# zerocam2S_revD.net
KiCad netlist of a schematic drawn in EAGLE
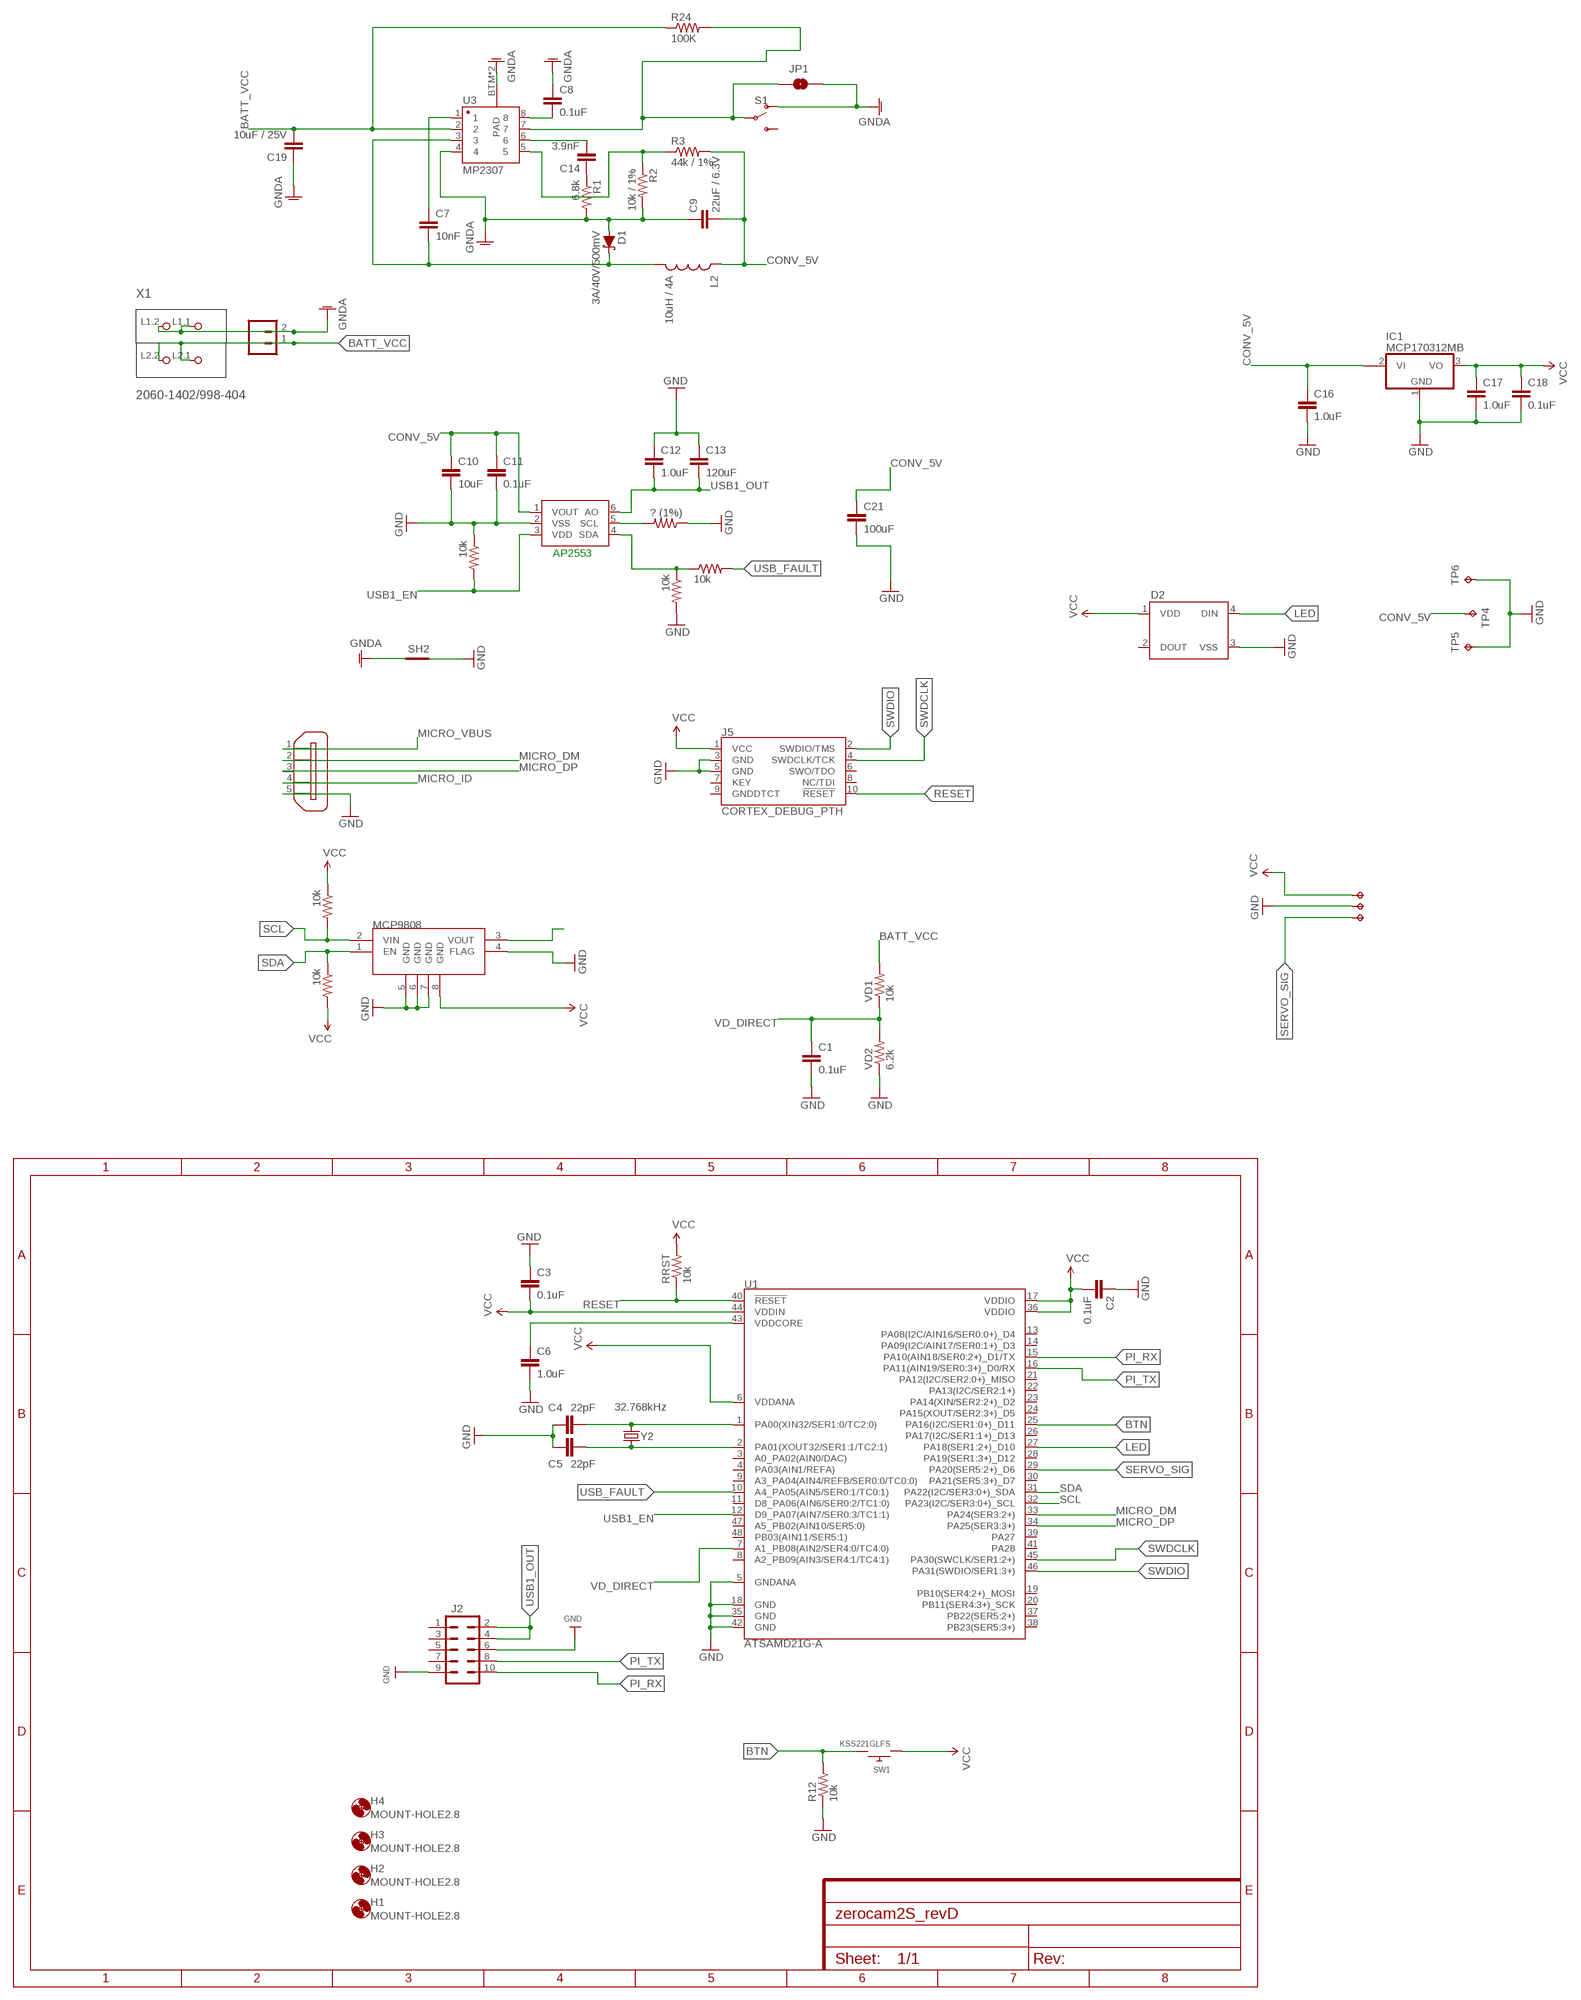
[diagram p0: schematic, sheet 1]

(export (version "E")
  (design (tool "Eeschema 10.0.6"))
  (components
    (comp (ref "AP2553")
      (value "MCP4725")
      (footprint "eagle-import:SOT23-6")
      (libsource (lib "eagle-import") (part "MCP4725SOT-23"))
    )
    (comp (ref "C1")
      (value "0.1uF")
      (footprint "eagle-import:0805")
      (libsource (lib "eagle-import") (part "CAP0805"))
    )
    (comp (ref "C2")
      (value "0.1uF")
      (footprint "eagle-import:0805")
      (libsource (lib "eagle-import") (part "1.0UF-0805-25V-10%"))
    )
    (comp (ref "C3")
      (value "0.1uF")
      (footprint "eagle-import:0805")
      (libsource (lib "eagle-import") (part "1.0UF-0805-25V-10%"))
    )
    (comp (ref "C4")
      (value "22pF")
      (footprint "eagle-import:0805")
      (libsource (lib "eagle-import") (part "SparkFun-Passives_CAP0805"))
    )
    (comp (ref "C5")
      (value "22pF")
      (footprint "eagle-import:0805")
      (libsource (lib "eagle-import") (part "SparkFun-Passives_CAP0805"))
    )
    (comp (ref "C6")
      (value "1.0uF")
      (footprint "eagle-import:0805")
      (libsource (lib "eagle-import") (part "1.0UF-0805-25V-10%"))
    )
    (comp (ref "C7")
      (value "10nF")
      (footprint "eagle-import:0805")
      (libsource (lib "eagle-import") (part "CAP0805"))
    )
    (comp (ref "C8")
      (value "0.1uF")
      (footprint "eagle-import:1206")
      (libsource (lib "eagle-import") (part "CAP1206"))
    )
    (comp (ref "C9")
      (value "22uF / 6.3V")
      (footprint "eagle-import:1210")
      (libsource (lib "eagle-import") (part "CAP1210"))
    )
    (comp (ref "C10")
      (value "10uF")
      (footprint "eagle-import:0805")
      (libsource (lib "eagle-import") (part "1.0UF-0805-25V-10%"))
    )
    (comp (ref "C11")
      (value "0.1uF")
      (footprint "eagle-import:0805")
      (libsource (lib "eagle-import") (part "1.0UF-0805-25V-10%"))
    )
    (comp (ref "C12")
      (value "1.0uF")
      (footprint "eagle-import:1206")
      (libsource (lib "eagle-import") (part "1.0UF-1206-50V-10%"))
    )
    (comp (ref "C13")
      (value "120uF")
      (footprint "eagle-import:1206")
      (libsource (lib "eagle-import") (part "1.0UF-1206-50V-10%"))
    )
    (comp (ref "C14")
      (value "3.9nF")
      (footprint "eagle-import:1206")
      (libsource (lib "eagle-import") (part "CAP1206"))
    )
    (comp (ref "C16")
      (value "1.0uF")
      (footprint "eagle-import:0805")
      (libsource (lib "eagle-import") (part "1.0UF-0805-25V-10%"))
    )
    (comp (ref "C17")
      (value "1.0uF")
      (footprint "eagle-import:1206")
      (libsource (lib "eagle-import") (part "1.0UF-1206-50V-10%"))
    )
    (comp (ref "C18")
      (value "0.1uF")
      (footprint "eagle-import:0805")
      (libsource (lib "eagle-import") (part "1.0UF-0805-25V-10%"))
    )
    (comp (ref "C19")
      (value "10uF / 25V")
      (footprint "eagle-import:1210")
      (libsource (lib "eagle-import") (part "CAP1210"))
    )
    (comp (ref "C21")
      (value "100uF")
      (footprint "eagle-import:1210")
      (libsource (lib "eagle-import") (part "10UF-1210-50V-20%"))
    )
    (comp (ref "D1")
      (value "3A/40V/500mV")
      (footprint "eagle-import:SMA-DIODE")
      (libsource (lib "eagle-import") (part "DIODE-SCHOTTKY-B340A"))
    )
    (comp (ref "D2")
      (value "WS2812B")
      (footprint "eagle-import:WS2812B")
      (libsource (lib "eagle-import") (part "WS2812B"))
    )
    (comp (ref "H1")
      (value "MOUNT-HOLE2.8")
      (footprint "eagle-import:2,8")
      (libsource (lib "eagle-import") (part "MOUNT-HOLE2.8"))
    )
    (comp (ref "H2")
      (value "MOUNT-HOLE2.8")
      (footprint "eagle-import:2,8")
      (libsource (lib "eagle-import") (part "MOUNT-HOLE2.8"))
    )
    (comp (ref "H3")
      (value "MOUNT-HOLE2.8")
      (footprint "eagle-import:2,8")
      (libsource (lib "eagle-import") (part "MOUNT-HOLE2.8"))
    )
    (comp (ref "H4")
      (value "MOUNT-HOLE2.8")
      (footprint "eagle-import:2,8")
      (libsource (lib "eagle-import") (part "MOUNT-HOLE2.8"))
    )
    (comp (ref "IC1")
      (value "MCP170312MB")
      (footprint "eagle-import:SOT89")
      (libsource (lib "eagle-import") (part "MCP1703MB12"))
    )
    (comp (ref "J1")
      (value "CONN_023.5MM-NO_SILK")
      (footprint "eagle-import:SCREWTERMINAL-3.5MM-2-NS")
      (libsource (lib "eagle-import") (part "CONN_023.5MM-NO_SILK"))
    )
    (comp (ref "J2")
      (value "M05X2PTH")
      (footprint "eagle-import:AVR_ICSP")
      (libsource (lib "eagle-import") (part "M05X2PTH"))
    )
    (comp (ref "J5")
      (value "CORTEX_DEBUG_PTH")
      (footprint "eagle-import:2X5-PTH-1.27MM")
      (libsource (lib "eagle-import") (part "CORTEX_DEBUG_PTH"))
    )
    (comp (ref "JP1")
      (value "JUMPER-SMT_2_NO_NO-SILK")
      (footprint "eagle-import:SMT-JUMPER_2_NO_NO-SILK")
      (libsource (lib "eagle-import") (part "JUMPER-SMT_2_NO_NO-SILK"))
    )
    (comp (ref "L2")
      (value "10uH / 4A")
      (footprint "eagle-import:SRU1038")
      (libsource (lib "eagle-import") (part "INDUCTORSRU1038"))
    )
    (comp (ref "MCP9808")
      (value "V_REG_MIC5216")
      (footprint "eagle-import:MSOP8")
      (libsource (lib "eagle-import") (part "V_REG_MIC5216"))
    )
    (comp (ref "R1")
      (value "6.8k")
      (footprint "eagle-import:1206")
      (libsource (lib "eagle-import") (part "SparkFun-Resistors_RESISTOR1206"))
    )
    (comp (ref "R2")
      (value "10k / 1%")
      (footprint "eagle-import:1206")
      (libsource (lib "eagle-import") (part "SparkFun-Resistors_RESISTOR1206"))
    )
    (comp (ref "R3")
      (value "44k / 1%")
      (footprint "eagle-import:1206")
      (libsource (lib "eagle-import") (part "SparkFun-Resistors_RESISTOR1206"))
    )
    (comp (ref "R12")
      (value "10k")
      (footprint "eagle-import:0805")
      (libsource (lib "eagle-import") (part "RESISTOR0805-RES"))
    )
    (comp (ref "R24")
      (value "100K")
      (footprint "eagle-import:1206")
      (libsource (lib "eagle-import") (part "SparkFun-Resistors_RESISTOR1206"))
    )
    (comp (ref "RRST")
      (value "10k")
      (footprint "eagle-import:0805")
      (libsource (lib "eagle-import") (part "RESISTOR0805-RES"))
    )
    (comp (ref "R_I2C_1")
      (value "10k")
      (footprint "eagle-import:0805")
      (libsource (lib "eagle-import") (part "RESISTOR0805-RES"))
    )
    (comp (ref "R_I2C_2")
      (value "10k")
      (footprint "eagle-import:0805")
      (libsource (lib "eagle-import") (part "RESISTOR0805-RES"))
    )
    (comp (ref "R_MOSFET_USB1")
      (value "? (1%)")
      (footprint "eagle-import:0805")
      (libsource (lib "eagle-import") (part "RESISTOR0805-RES"))
    )
    (comp (ref "R_MOSFET_USB2")
      (value "10k")
      (footprint "eagle-import:0805")
      (libsource (lib "eagle-import") (part "RESISTOR0805-RES"))
    )
    (comp (ref "R_MOSFET_USB3")
      (value "10k")
      (footprint "eagle-import:0805")
      (libsource (lib "eagle-import") (part "RESISTOR0805-RES"))
    )
    (comp (ref "R_MOSFET_USB4")
      (value "10k")
      (footprint "eagle-import:0805")
      (libsource (lib "eagle-import") (part "RESISTOR0805-RES"))
    )
    (comp (ref "S1")
      (value "SWITCH-SPDT-SMD-RIGHT-ANGLE")
      (footprint "eagle-import:SWITCH_SPST_SMD_A")
      (libsource (lib "eagle-import") (part "SWITCH-SPDT-SMD-RIGHT-ANGLE"))
    )
    (comp (ref "SH2")
      (value "SHORT-HT5")
      (footprint "eagle-import:SHORT_TOP-50")
      (libsource (lib "eagle-import") (part "SHORT-HT5"))
    )
    (comp (ref "SW1")
      (value "KSS221GLFS")
      (footprint "eagle-import:BTN_CK_KSS")
      (libsource (lib "eagle-import") (part "SWITCH_PUSHBUTTONC&K_KSS"))
    )
    (comp (ref "TP1")
      (value "TPPAD1-13Y")
      (footprint "eagle-import:P1-13Y")
      (libsource (lib "eagle-import") (part "TPPAD1-13Y"))
    )
    (comp (ref "TP2")
      (value "TPPAD1-13Y")
      (footprint "eagle-import:P1-13Y")
      (libsource (lib "eagle-import") (part "TPPAD1-13Y"))
    )
    (comp (ref "TP3")
      (value "TPPAD1-13Y")
      (footprint "eagle-import:P1-13Y")
      (libsource (lib "eagle-import") (part "TPPAD1-13Y"))
    )
    (comp (ref "TP4")
      (value "TPB2,54")
      (footprint "eagle-import:B2,54")
      (libsource (lib "eagle-import") (part "TPB2,54"))
    )
    (comp (ref "TP5")
      (value "TPB2,54")
      (footprint "eagle-import:B2,54")
      (libsource (lib "eagle-import") (part "TPB2,54"))
    )
    (comp (ref "TP6")
      (value "TPB2,54")
      (footprint "eagle-import:B2,54")
      (libsource (lib "eagle-import") (part "TPB2,54"))
    )
    (comp (ref "U1")
      (value "ATSAMD21G-A")
      (footprint "eagle-import:TQFP-48")
      (libsource (lib "eagle-import") (part "ATSAMD21G-A"))
    )
    (comp (ref "U3")
      (value "MP2307")
      (footprint "eagle-import:SO08")
      (libsource (lib "eagle-import") (part "GENERIC-SOIC8MSGEQ7N-FILTER"))
    )
    (comp (ref "VD1")
      (value "10k")
      (footprint "eagle-import:0805")
      (libsource (lib "eagle-import") (part "RESISTOR0805-RES"))
    )
    (comp (ref "VD2")
      (value "6.2k")
      (footprint "eagle-import:0805")
      (libsource (lib "eagle-import") (part "RESISTOR0805-RES"))
    )
    (comp (ref "X1")
      (value "2060-1402/998-404")
      (footprint "eagle-import:P-2060-1402_998-404")
      (libsource (lib "eagle-import") (part "2060-1402/998-404"))
    )
    (comp (ref "X2")
      (value "ZX62D-B-5PA8")
      (footprint "eagle-import:ZX62D-B-5PA8")
      (fields (field (name "MF") "Hirose"))
      (libsource (lib "eagle-import") (part "ZX62D-B-5PA8"))
    )
    (comp (ref "Y2")
      (value "32.768kHz")
      (footprint "eagle-import:CRYSTAL-SMD-3.2X1.5MM")
      (libsource (lib "eagle-import") (part "CRYSTAL3.2X1.5MM"))
    )
  )
  (nets
    (net (code "1") (name "/CONV_5V") (class "Default")
      (node (ref "AP2553") (pin "1") (pinfunction "VOUT_1") (pintype "bidirectional"))
      (node (ref "C10") (pin "1") (pinfunction "1_1") (pintype "passive"))
      (node (ref "C11") (pin "1") (pinfunction "1_1") (pintype "passive"))
      (node (ref "C16") (pin "1") (pinfunction "1_1") (pintype "passive"))
      (node (ref "C21") (pin "1") (pinfunction "1_1") (pintype "passive"))
      (node (ref "C9") (pin "2") (pinfunction "2_2") (pintype "passive"))
      (node (ref "IC1") (pin "2@1") (pinfunction "VI1_2@1") (pintype "input"))
      (node (ref "L2") (pin "1") (pinfunction "1_1") (pintype "passive"))
      (node (ref "R3") (pin "2") (pinfunction "2_2") (pintype "passive"))
      (node (ref "TP4") (pin "TP") (pinfunction "TP_TP") (pintype "input"))
    )
    (net (code "2") (name "/MICRO_DM") (class "Default")
      (node (ref "U1") (pin "33") (pinfunction "PA24(SER3:2+)_33") (pintype "bidirectional"))
      (node (ref "X2") (pin "2") (pinfunction "2_2") (pintype "passive"))
    )
    (net (code "3") (name "/MICRO_DP") (class "Default")
      (node (ref "U1") (pin "34") (pinfunction "PA25(SER3:3+)_34") (pintype "bidirectional"))
      (node (ref "X2") (pin "3") (pinfunction "3_3") (pintype "passive"))
    )
    (net (code "4") (name "/MICRO_ID") (class "Default")
      (node (ref "X2") (pin "4") (pinfunction "4_4") (pintype "passive"))
    )
    (net (code "5") (name "/MICRO_VBUS") (class "Default")
      (node (ref "X2") (pin "1") (pinfunction "1_1") (pintype "passive"))
    )
    (net (code "6") (name "/USB1_EN") (class "Default")
      (node (ref "AP2553") (pin "3") (pinfunction "VDD_3") (pintype "bidirectional"))
      (node (ref "R_MOSFET_USB3") (pin "2") (pinfunction "2_2") (pintype "passive"))
      (node (ref "U1") (pin "12") (pinfunction "D9_PA07(AIN7/SER0:3/TC1:1)_12") (pintype "bidirectional"))
    )
    (net (code "7") (name "/VD_DIRECT") (class "Default")
      (node (ref "C1") (pin "1") (pinfunction "1_1") (pintype "passive"))
      (node (ref "U1") (pin "7") (pinfunction "A1_PB08(AIN2/SER4:0/TC4:0)_7") (pintype "bidirectional"))
      (node (ref "VD1") (pin "1") (pinfunction "1_1") (pintype "passive"))
      (node (ref "VD2") (pin "2") (pinfunction "2_2") (pintype "passive"))
    )
    (net (code "8") (name "BATT_VCC") (class "Default")
      (node (ref "C19") (pin "2") (pinfunction "2_2") (pintype "passive"))
      (node (ref "J1") (pin "1") (pinfunction "1_1") (pintype "passive"))
      (node (ref "R24") (pin "1") (pinfunction "1_1") (pintype "passive"))
      (node (ref "U3") (pin "2") (pinfunction "2_2") (pintype "bidirectional"))
      (node (ref "VD1") (pin "2") (pinfunction "2_2") (pintype "passive"))
      (node (ref "X1") (pin "L2.1") (pinfunction "P2.1_L2.1") (pintype "bidirectional"))
      (node (ref "X1") (pin "L2.2") (pinfunction "P2.2_L2.2") (pintype "bidirectional"))
    )
    (net (code "9") (name "BTN") (class "Default")
      (node (ref "R12") (pin "2") (pinfunction "2_2") (pintype "passive"))
      (node (ref "SW1") (pin "P$2") (pinfunction "P$2_P$2") (pintype "passive"))
      (node (ref "U1") (pin "25") (pinfunction "PA16(I2C/SER1:0+)_D11_25") (pintype "bidirectional"))
    )
    (net (code "10") (name "GND") (class "Default")
      (node (ref "AP2553") (pin "2") (pinfunction "VSS_2") (pintype "bidirectional"))
      (node (ref "C1") (pin "2") (pinfunction "2_2") (pintype "passive"))
      (node (ref "C10") (pin "2") (pinfunction "2_2") (pintype "passive"))
      (node (ref "C11") (pin "2") (pinfunction "2_2") (pintype "passive"))
      (node (ref "C12") (pin "1") (pinfunction "1_1") (pintype "passive"))
      (node (ref "C13") (pin "1") (pinfunction "1_1") (pintype "passive"))
      (node (ref "C16") (pin "2") (pinfunction "2_2") (pintype "passive"))
      (node (ref "C17") (pin "2") (pinfunction "2_2") (pintype "passive"))
      (node (ref "C18") (pin "2") (pinfunction "2_2") (pintype "passive"))
      (node (ref "C2") (pin "1") (pinfunction "1_1") (pintype "passive"))
      (node (ref "C21") (pin "2") (pinfunction "2_2") (pintype "passive"))
      (node (ref "C3") (pin "1") (pinfunction "1_1") (pintype "passive"))
      (node (ref "C4") (pin "1") (pinfunction "1_1") (pintype "passive"))
      (node (ref "C5") (pin "1") (pinfunction "1_1") (pintype "passive"))
      (node (ref "C6") (pin "2") (pinfunction "2_2") (pintype "passive"))
      (node (ref "D2") (pin "3") (pinfunction "VSS_3") (pintype "power_in"))
      (node (ref "IC1") (pin "1") (pinfunction "GND_1") (pintype "passive"))
      (node (ref "J2") (pin "6") (pinfunction "6_6") (pintype "passive"))
      (node (ref "J2") (pin "9") (pinfunction "9_9") (pintype "passive"))
      (node (ref "J5") (pin "3") (pinfunction "GND_3") (pintype "bidirectional"))
      (node (ref "J5") (pin "5") (pinfunction "GND_5") (pintype "bidirectional"))
      (node (ref "MCP9808") (pin "4") (pinfunction "FLAG_4") (pintype "bidirectional"))
      (node (ref "MCP9808") (pin "5") (pinfunction "GND_5") (pintype "bidirectional"))
      (node (ref "MCP9808") (pin "6") (pinfunction "GND_6") (pintype "bidirectional"))
      (node (ref "MCP9808") (pin "7") (pinfunction "GND_7") (pintype "bidirectional"))
      (node (ref "R12") (pin "1") (pinfunction "1_1") (pintype "passive"))
      (node (ref "R_MOSFET_USB1") (pin "1") (pinfunction "1_1") (pintype "passive"))
      (node (ref "R_MOSFET_USB2") (pin "2") (pinfunction "2_2") (pintype "passive"))
      (node (ref "R_MOSFET_USB3") (pin "1") (pinfunction "1_1") (pintype "passive"))
      (node (ref "SH2") (pin "2") (pinfunction "P$2_2") (pintype "bidirectional"))
      (node (ref "TP2") (pin "TP") (pinfunction "TP_TP") (pintype "input"))
      (node (ref "TP5") (pin "TP") (pinfunction "TP_TP") (pintype "input"))
      (node (ref "TP6") (pin "TP") (pinfunction "TP_TP") (pintype "input"))
      (node (ref "U1") (pin "18") (pinfunction "GND_18") (pintype "bidirectional"))
      (node (ref "U1") (pin "35") (pinfunction "GND_35") (pintype "bidirectional"))
      (node (ref "U1") (pin "42") (pinfunction "GND_42") (pintype "bidirectional"))
      (node (ref "U1") (pin "5") (pinfunction "GNDANA_5") (pintype "bidirectional"))
      (node (ref "VD2") (pin "1") (pinfunction "1_1") (pintype "passive"))
      (node (ref "X2") (pin "5") (pinfunction "5_5") (pintype "passive"))
    )
    (net (code "11") (name "GNDA") (class "Default")
      (node (ref "C19") (pin "1") (pinfunction "1_1") (pintype "passive"))
      (node (ref "C8") (pin "1") (pinfunction "1_1") (pintype "passive"))
      (node (ref "C9") (pin "1") (pinfunction "1_1") (pintype "passive"))
      (node (ref "D1") (pin "A") (pinfunction "A_A") (pintype "passive"))
      (node (ref "J1") (pin "2") (pinfunction "2_2") (pintype "passive"))
      (node (ref "JP1") (pin "2") (pinfunction "2_2") (pintype "passive"))
      (node (ref "R1") (pin "2") (pinfunction "2_2") (pintype "passive"))
      (node (ref "R2") (pin "2") (pinfunction "2_2") (pintype "passive"))
      (node (ref "S1") (pin "1") (pinfunction "O_1") (pintype "passive"))
      (node (ref "SH2") (pin "1") (pinfunction "P$1_1") (pintype "bidirectional"))
      (node (ref "U3") (pin "4") (pinfunction "4_4") (pintype "bidirectional"))
      (node (ref "U3") (pin "BTM") (pinfunction "PAD_BTM") (pintype "bidirectional"))
      (node (ref "U3") (pin "P$1") (pinfunction "PAD_P$1") (pintype "bidirectional"))
      (node (ref "X1") (pin "L1.1") (pinfunction "P1.1_L1.1") (pintype "bidirectional"))
      (node (ref "X1") (pin "L1.2") (pinfunction "P1.2_L1.2") (pintype "bidirectional"))
    )
    (net (code "12") (name "LED") (class "Default")
      (node (ref "D2") (pin "4") (pinfunction "DIN_4") (pintype "input"))
      (node (ref "U1") (pin "27") (pinfunction "PA18(SER1:2+)_D10_27") (pintype "bidirectional"))
    )
    (net (code "13") (name "Net-(AP2553-SCL)") (class "Default")
      (node (ref "AP2553") (pin "5") (pinfunction "SCL_5") (pintype "bidirectional"))
      (node (ref "R_MOSFET_USB1") (pin "2") (pinfunction "2_2") (pintype "passive"))
    )
    (net (code "14") (name "Net-(AP2553-SDA)") (class "Default")
      (node (ref "AP2553") (pin "4") (pinfunction "SDA_4") (pintype "bidirectional"))
      (node (ref "R_MOSFET_USB2") (pin "1") (pinfunction "1_1") (pintype "passive"))
      (node (ref "R_MOSFET_USB4") (pin "1") (pinfunction "1_1") (pintype "passive"))
    )
    (net (code "15") (name "Net-(C7-Pad1)") (class "Default")
      (node (ref "C7") (pin "1") (pinfunction "1_1") (pintype "passive"))
      (node (ref "U3") (pin "1") (pinfunction "1_1") (pintype "bidirectional"))
    )
    (net (code "16") (name "Net-(C7-Pad2)") (class "Default")
      (node (ref "C7") (pin "2") (pinfunction "2_2") (pintype "passive"))
      (node (ref "D1") (pin "C") (pinfunction "C_C") (pintype "passive"))
      (node (ref "L2") (pin "2") (pinfunction "2_2") (pintype "passive"))
      (node (ref "U3") (pin "3") (pinfunction "3_3") (pintype "bidirectional"))
    )
    (net (code "17") (name "Net-(C8-Pad2)") (class "Default")
      (node (ref "C8") (pin "2") (pinfunction "2_2") (pintype "passive"))
      (node (ref "U3") (pin "8") (pinfunction "8_8") (pintype "bidirectional"))
    )
    (net (code "18") (name "Net-(C14-Pad1)") (class "Default")
      (node (ref "C14") (pin "1") (pinfunction "1_1") (pintype "passive"))
      (node (ref "R1") (pin "1") (pinfunction "1_1") (pintype "passive"))
    )
    (net (code "19") (name "Net-(C14-Pad2)") (class "Default")
      (node (ref "C14") (pin "2") (pinfunction "2_2") (pintype "passive"))
      (node (ref "U3") (pin "6") (pinfunction "6_6") (pintype "bidirectional"))
    )
    (net (code "20") (name "Net-(R2-Pad1)") (class "Default")
      (node (ref "R2") (pin "1") (pinfunction "1_1") (pintype "passive"))
      (node (ref "R3") (pin "1") (pinfunction "1_1") (pintype "passive"))
      (node (ref "U3") (pin "5") (pinfunction "5_5") (pintype "bidirectional"))
    )
    (net (code "21") (name "Net-(S1-P)") (class "Default")
      (node (ref "JP1") (pin "1") (pinfunction "1_1") (pintype "passive"))
      (node (ref "R24") (pin "2") (pinfunction "2_2") (pintype "passive"))
      (node (ref "S1") (pin "2") (pinfunction "P_2") (pintype "passive"))
      (node (ref "U3") (pin "7") (pinfunction "7_7") (pintype "bidirectional"))
    )
    (net (code "22") (name "Net-(U1-PA00(XIN32{slash}SER1:0{slash}TC2:0))") (class "Default")
      (node (ref "C4") (pin "2") (pinfunction "2_2") (pintype "passive"))
      (node (ref "U1") (pin "1") (pinfunction "PA00(XIN32/SER1:0/TC2:0)_1") (pintype "bidirectional"))
      (node (ref "Y2") (pin "P$2") (pinfunction "2_P$2") (pintype "passive"))
    )
    (net (code "23") (name "Net-(U1-PA01(XOUT32{slash}SER1:1{slash}TC2:1))") (class "Default")
      (node (ref "C5") (pin "2") (pinfunction "2_2") (pintype "passive"))
      (node (ref "U1") (pin "2") (pinfunction "PA01(XOUT32/SER1:1/TC2:1)_2") (pintype "bidirectional"))
      (node (ref "Y2") (pin "P$1") (pinfunction "1_P$1") (pintype "passive"))
    )
    (net (code "24") (name "Net-(U1-VDDCORE)") (class "Default")
      (node (ref "C6") (pin "1") (pinfunction "1_1") (pintype "passive"))
      (node (ref "U1") (pin "43") (pinfunction "VDDCORE_43") (pintype "bidirectional"))
    )
    (net (code "25") (name "PI_RX") (class "Default")
      (node (ref "J2") (pin "10") (pinfunction "10_10") (pintype "passive"))
      (node (ref "U1") (pin "15") (pinfunction "PA10(AIN18/SER0:2+)_D1/TX_15") (pintype "bidirectional"))
    )
    (net (code "26") (name "PI_TX") (class "Default")
      (node (ref "J2") (pin "8") (pinfunction "8_8") (pintype "passive"))
      (node (ref "U1") (pin "16") (pinfunction "PA11(AIN19/SER0:3+)_D0/RX_16") (pintype "bidirectional"))
    )
    (net (code "27") (name "RESET") (class "Default")
      (node (ref "J5") (pin "10") (pinfunction "~{RESET}_10") (pintype "bidirectional"))
      (node (ref "RRST") (pin "1") (pinfunction "1_1") (pintype "passive"))
      (node (ref "U1") (pin "40") (pinfunction "~{RESET}_40") (pintype "bidirectional"))
    )
    (net (code "28") (name "SCL") (class "Default")
      (node (ref "MCP9808") (pin "2") (pinfunction "VIN_2") (pintype "bidirectional"))
      (node (ref "R_I2C_1") (pin "2") (pinfunction "2_2") (pintype "passive"))
      (node (ref "U1") (pin "32") (pinfunction "PA23(I2C/SER3:0+)_SCL_32") (pintype "bidirectional"))
    )
    (net (code "29") (name "SDA") (class "Default")
      (node (ref "MCP9808") (pin "1") (pinfunction "EN_1") (pintype "bidirectional"))
      (node (ref "R_I2C_2") (pin "1") (pinfunction "1_1") (pintype "passive"))
      (node (ref "U1") (pin "31") (pinfunction "PA22(I2C/SER3:0+)_SDA_31") (pintype "bidirectional"))
    )
    (net (code "30") (name "SERVO_SIG") (class "Default")
      (node (ref "TP3") (pin "TP") (pinfunction "TP_TP") (pintype "input"))
      (node (ref "U1") (pin "29") (pinfunction "PA20(SER5:2+)_D6_29") (pintype "bidirectional"))
    )
    (net (code "31") (name "SWDCLK") (class "Default")
      (node (ref "J5") (pin "4") (pinfunction "SWDCLK/TCK_4") (pintype "bidirectional"))
      (node (ref "U1") (pin "45") (pinfunction "PA30(SWCLK/SER1:2+)_45") (pintype "bidirectional"))
    )
    (net (code "32") (name "SWDIO") (class "Default")
      (node (ref "J5") (pin "2") (pinfunction "SWDIO/TMS_2") (pintype "bidirectional"))
      (node (ref "U1") (pin "46") (pinfunction "PA31(SWDIO/SER1:3+)_46") (pintype "bidirectional"))
    )
    (net (code "33") (name "USB1_OUT") (class "Default")
      (node (ref "AP2553") (pin "6") (pinfunction "AO_6") (pintype "bidirectional"))
      (node (ref "C12") (pin "2") (pinfunction "2_2") (pintype "passive"))
      (node (ref "C13") (pin "2") (pinfunction "2_2") (pintype "passive"))
      (node (ref "J2") (pin "2") (pinfunction "2_2") (pintype "passive"))
      (node (ref "J2") (pin "4") (pinfunction "4_4") (pintype "passive"))
    )
    (net (code "34") (name "USB_FAULT") (class "Default")
      (node (ref "R_MOSFET_USB4") (pin "2") (pinfunction "2_2") (pintype "passive"))
      (node (ref "U1") (pin "10") (pinfunction "A4_PA05(AIN5/SER0:1/TC0:1)_10") (pintype "bidirectional"))
    )
    (net (code "35") (name "VCC") (class "Default")
      (node (ref "C17") (pin "1") (pinfunction "1_1") (pintype "passive"))
      (node (ref "C18") (pin "1") (pinfunction "1_1") (pintype "passive"))
      (node (ref "C2") (pin "2") (pinfunction "2_2") (pintype "passive"))
      (node (ref "C3") (pin "2") (pinfunction "2_2") (pintype "passive"))
      (node (ref "D2") (pin "1") (pinfunction "VDD_1") (pintype "power_in"))
      (node (ref "IC1") (pin "3") (pinfunction "VO_3") (pintype "passive"))
      (node (ref "J5") (pin "1") (pinfunction "VCC_1") (pintype "bidirectional"))
      (node (ref "MCP9808") (pin "8") (pinfunction "GND_8") (pintype "bidirectional"))
      (node (ref "RRST") (pin "2") (pinfunction "2_2") (pintype "passive"))
      (node (ref "R_I2C_1") (pin "1") (pinfunction "1_1") (pintype "passive"))
      (node (ref "R_I2C_2") (pin "2") (pinfunction "2_2") (pintype "passive"))
      (node (ref "SW1") (pin "P$1") (pinfunction "P$1_P$1") (pintype "passive"))
      (node (ref "TP1") (pin "TP") (pinfunction "TP_TP") (pintype "input"))
      (node (ref "U1") (pin "17") (pinfunction "VDDIO_17") (pintype "bidirectional"))
      (node (ref "U1") (pin "36") (pinfunction "VDDIO_36") (pintype "bidirectional"))
      (node (ref "U1") (pin "44") (pinfunction "VDDIN_44") (pintype "bidirectional"))
      (node (ref "U1") (pin "6") (pinfunction "VDDANA_6") (pintype "bidirectional"))
    )
    (net (code "36") (name "unconnected-(D2-DOUT-Pad2)") (class "Default")
      (node (ref "D2") (pin "2") (pinfunction "DOUT_2") (pintype "output"))
    )
    (net (code "37") (name "unconnected-(IC1-VI-Pad2)") (class "Default")
      (node (ref "IC1") (pin "2") (pinfunction "VI_2") (pintype "input"))
    )
    (net (code "38") (name "unconnected-(J2-Pad1)") (class "Default")
      (node (ref "J2") (pin "1") (pinfunction "1_1") (pintype "passive"))
    )
    (net (code "39") (name "unconnected-(J2-Pad3)") (class "Default")
      (node (ref "J2") (pin "3") (pinfunction "3_3") (pintype "passive"))
    )
    (net (code "40") (name "unconnected-(J2-Pad5)") (class "Default")
      (node (ref "J2") (pin "5") (pinfunction "5_5") (pintype "passive"))
    )
    (net (code "41") (name "unconnected-(J2-Pad7)") (class "Default")
      (node (ref "J2") (pin "7") (pinfunction "7_7") (pintype "passive"))
    )
    (net (code "42") (name "unconnected-(J5-GNDDTCT-Pad9)") (class "Default")
      (node (ref "J5") (pin "9") (pinfunction "GNDDTCT_9") (pintype "bidirectional"))
    )
    (net (code "43") (name "unconnected-(J5-KEY-Pad7)") (class "Default")
      (node (ref "J5") (pin "7") (pinfunction "KEY_7") (pintype "bidirectional"))
    )
    (net (code "44") (name "unconnected-(J5-NC{slash}TDI-Pad8)") (class "Default")
      (node (ref "J5") (pin "8") (pinfunction "NC/TDI_8") (pintype "bidirectional"))
    )
    (net (code "45") (name "unconnected-(J5-SWO{slash}TDO-Pad6)") (class "Default")
      (node (ref "J5") (pin "6") (pinfunction "SWO/TDO_6") (pintype "bidirectional"))
    )
    (net (code "46") (name "unconnected-(MCP9808-VOUT-Pad3)") (class "Default")
      (node (ref "MCP9808") (pin "3") (pinfunction "VOUT_3") (pintype "bidirectional"))
    )
    (net (code "47") (name "unconnected-(S1-S-Pad3)") (class "Default")
      (node (ref "S1") (pin "3") (pinfunction "S_3") (pintype "passive"))
    )
    (net (code "48") (name "unconnected-(U1-A0_PA02(AIN0{slash}DAC)-Pad3)") (class "Default")
      (node (ref "U1") (pin "3") (pinfunction "A0_PA02(AIN0/DAC)_3") (pintype "bidirectional"))
    )
    (net (code "49") (name "unconnected-(U1-A2_PB09(AIN3{slash}SER4:1{slash}TC4:1)-Pad8)") (class "Default")
      (node (ref "U1") (pin "8") (pinfunction "A2_PB09(AIN3/SER4:1/TC4:1)_8") (pintype "bidirectional"))
    )
    (net (code "50") (name "unconnected-(U1-A3_PA04(AIN4{slash}REFB{slash}SER0:0{slash}TC0:0)-Pad9)") (class "Default")
      (node (ref "U1") (pin "9") (pinfunction "A3_PA04(AIN4/REFB/SER0:0/TC0:0)_9") (pintype "bidirectional"))
    )
    (net (code "51") (name "unconnected-(U1-A5_PB02(AIN10{slash}SER5:0)-Pad47)") (class "Default")
      (node (ref "U1") (pin "47") (pinfunction "A5_PB02(AIN10/SER5:0)_47") (pintype "bidirectional"))
    )
    (net (code "52") (name "unconnected-(U1-D8_PA06(AIN6{slash}SER0:2{slash}TC1:0)-Pad11)") (class "Default")
      (node (ref "U1") (pin "11") (pinfunction "D8_PA06(AIN6/SER0:2/TC1:0)_11") (pintype "bidirectional"))
    )
    (net (code "53") (name "unconnected-(U1-PA03(AIN1{slash}REFA)-Pad4)") (class "Default")
      (node (ref "U1") (pin "4") (pinfunction "PA03(AIN1/REFA)_4") (pintype "bidirectional"))
    )
    (net (code "54") (name "unconnected-(U1-PA08(I2C{slash}AIN16{slash}SER0:0+)_D4-Pad13)") (class "Default")
      (node (ref "U1") (pin "13") (pinfunction "PA08(I2C/AIN16/SER0:0+)_D4_13") (pintype "bidirectional"))
    )
    (net (code "55") (name "unconnected-(U1-PA09(I2C{slash}AIN17{slash}SER0:1+)_D3-Pad14)") (class "Default")
      (node (ref "U1") (pin "14") (pinfunction "PA09(I2C/AIN17/SER0:1+)_D3_14") (pintype "bidirectional"))
    )
    (net (code "56") (name "unconnected-(U1-PA12(I2C{slash}SER2:0+)_MISO-Pad21)") (class "Default")
      (node (ref "U1") (pin "21") (pinfunction "PA12(I2C/SER2:0+)_MISO_21") (pintype "bidirectional"))
    )
    (net (code "57") (name "unconnected-(U1-PA13(I2C{slash}SER2:1+)-Pad22)") (class "Default")
      (node (ref "U1") (pin "22") (pinfunction "PA13(I2C/SER2:1+)_22") (pintype "bidirectional"))
    )
    (net (code "58") (name "unconnected-(U1-PA14(XIN{slash}SER2:2+)_D2-Pad23)") (class "Default")
      (node (ref "U1") (pin "23") (pinfunction "PA14(XIN/SER2:2+)_D2_23") (pintype "bidirectional"))
    )
    (net (code "59") (name "unconnected-(U1-PA15(XOUT{slash}SER2:3+)_D5-Pad24)") (class "Default")
      (node (ref "U1") (pin "24") (pinfunction "PA15(XOUT/SER2:3+)_D5_24") (pintype "bidirectional"))
    )
    (net (code "60") (name "unconnected-(U1-PA17(I2C{slash}SER1:1+)_D13-Pad26)") (class "Default")
      (node (ref "U1") (pin "26") (pinfunction "PA17(I2C/SER1:1+)_D13_26") (pintype "bidirectional"))
    )
    (net (code "61") (name "unconnected-(U1-PA19(SER1:3+)_D12-Pad28)") (class "Default")
      (node (ref "U1") (pin "28") (pinfunction "PA19(SER1:3+)_D12_28") (pintype "bidirectional"))
    )
    (net (code "62") (name "unconnected-(U1-PA21(SER5:3+)_D7-Pad30)") (class "Default")
      (node (ref "U1") (pin "30") (pinfunction "PA21(SER5:3+)_D7_30") (pintype "bidirectional"))
    )
    (net (code "63") (name "unconnected-(U1-PA27-Pad39)") (class "Default")
      (node (ref "U1") (pin "39") (pinfunction "PA27_39") (pintype "bidirectional"))
    )
    (net (code "64") (name "unconnected-(U1-PA28-Pad41)") (class "Default")
      (node (ref "U1") (pin "41") (pinfunction "PA28_41") (pintype "bidirectional"))
    )
    (net (code "65") (name "unconnected-(U1-PB03(AIN11{slash}SER5:1)-Pad48)") (class "Default")
      (node (ref "U1") (pin "48") (pinfunction "PB03(AIN11/SER5:1)_48") (pintype "bidirectional"))
    )
    (net (code "66") (name "unconnected-(U1-PB10(SER4:2+)_MOSI-Pad19)") (class "Default")
      (node (ref "U1") (pin "19") (pinfunction "PB10(SER4:2+)_MOSI_19") (pintype "bidirectional"))
    )
    (net (code "67") (name "unconnected-(U1-PB11(SER4:3+)_SCK-Pad20)") (class "Default")
      (node (ref "U1") (pin "20") (pinfunction "PB11(SER4:3+)_SCK_20") (pintype "bidirectional"))
    )
    (net (code "68") (name "unconnected-(U1-PB22(SER5:2+)-Pad37)") (class "Default")
      (node (ref "U1") (pin "37") (pinfunction "PB22(SER5:2+)_37") (pintype "bidirectional"))
    )
    (net (code "69") (name "unconnected-(U1-PB23(SER5:3+)-Pad38)") (class "Default")
      (node (ref "U1") (pin "38") (pinfunction "PB23(SER5:3+)_38") (pintype "bidirectional"))
    )
  )
)
